# badge.net
KiCad netlist of a schematic drawn in EAGLE
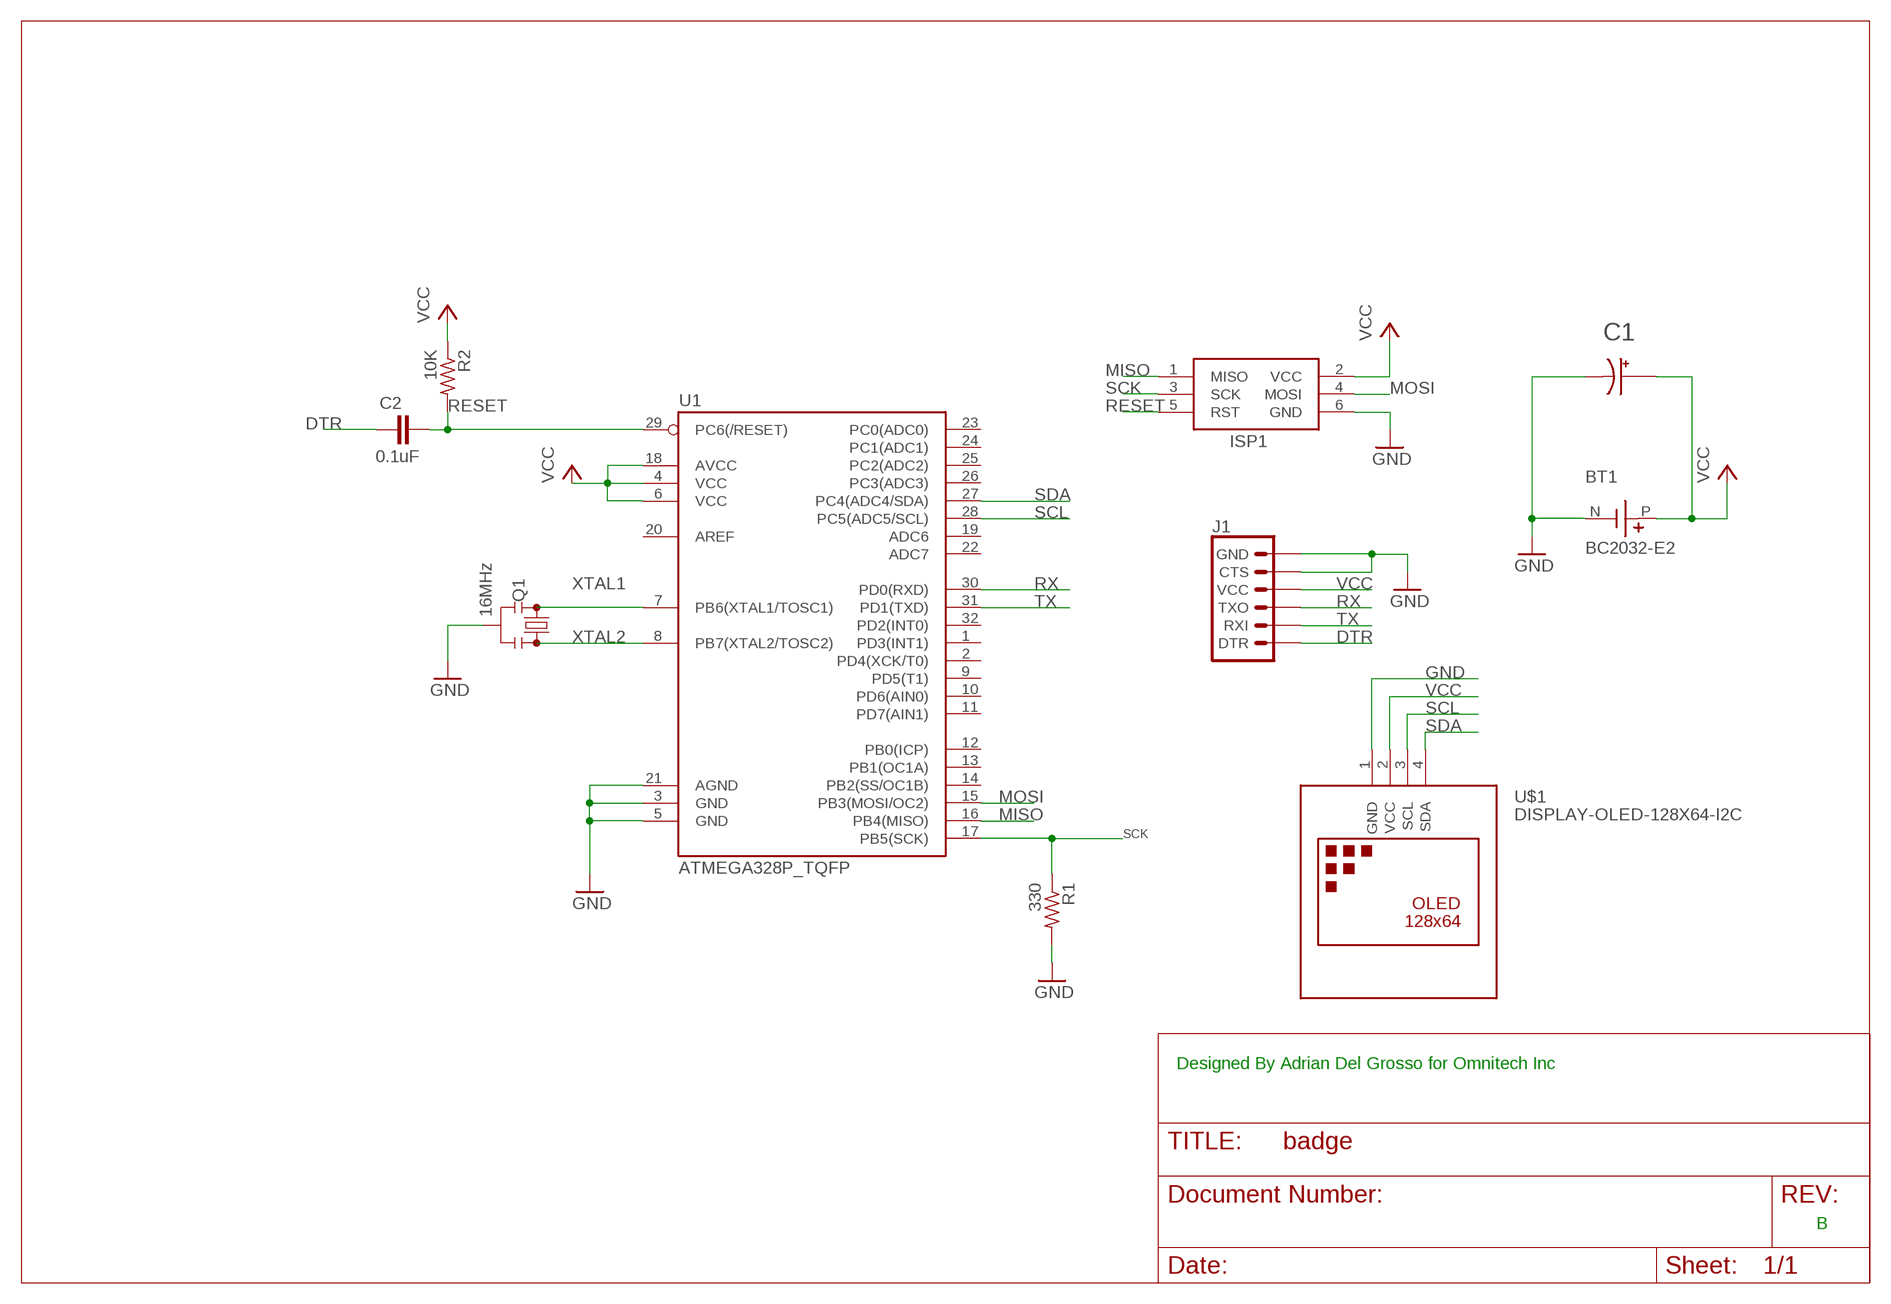
[diagram p0: schematic, sheet 1]

(export (version "E")
  (design (tool "Eeschema 10.0.6"))
  (components
    (comp (ref "BT1")
      (value "BC2032-E2")
      (footprint "eagle-import:MPD_BC2032-E2")
      (fields (field (name "DIGI-KEY_PART_NUMBER") "BC2032-E2-ND") (field (name "MF") "MPD _Memory"))
      (libsource (lib "eagle-import") (part "BC2032-E2"))
    )
    (comp (ref "C1")
      (value "RNE1C101MDS1PX")
      (footprint "eagle-import:CAPPRD200W50D500H1000")
      (fields (field (name "DIGI-KEY_PART_NUMBER") "493-3813-1-ND") (field (name "MF") "Nichicon"))
      (libsource (lib "eagle-import") (part "RNE1C101MDS1PX"))
    )
    (comp (ref "C2")
      (value "0.1uF")
      (footprint "eagle-import:0402")
      (libsource (lib "eagle-import") (part "0.1UF-0402-16V-10%"))
    )
    (comp (ref "ISP1")
      (value "AVRISP-6")
      (footprint "eagle-import:AVRISP")
      (libsource (lib "eagle-import") (part "AVRISP-6"))
    )
    (comp (ref "J1")
      (value "6_PIN_SERIAL_TARGETLONGPADS")
      (footprint "eagle-import:1X06_LONGPADS")
      (libsource (lib "eagle-import") (part "6_PIN_SERIAL_TARGETLONGPADS"))
    )
    (comp (ref "Q1")
      (value "16MHz")
      (footprint "eagle-import:RESONATOR-SMD-3.2X1.3")
      (libsource (lib "eagle-import") (part "RESONATOR-8MHZSMD_3.2X1.3"))
    )
    (comp (ref "R1")
      (value "330")
      (footprint "eagle-import:R0603")
      (libsource (lib "eagle-import") (part "R-US_R0603"))
    )
    (comp (ref "R2")
      (value "10K")
      (footprint "eagle-import:R0603")
      (libsource (lib "eagle-import") (part "R-US_R0603"))
    )
    (comp (ref "U$1")
      (value "DISPLAY-OLED-128X64-I2C")
      (footprint "eagle-import:DISPLAY-OLED-128X64-I2C")
      (libsource (lib "eagle-import") (part "DISPLAY-OLED-128X64-I2C"))
    )
    (comp (ref "U1")
      (value "ATMEGA328P_TQFP")
      (footprint "eagle-import:TQFP32-08")
      (libsource (lib "eagle-import") (part "ATMEGA328P_TQFP"))
    )
  )
  (nets
    (net (code "1") (name "/DTR") (class "Default")
      (node (ref "C2") (pin "1") (pinfunction "1_1") (pintype "passive"))
      (node (ref "J1") (pin "1") (pinfunction "DTR_1") (pintype "passive"))
    )
    (net (code "2") (name "/MISO") (class "Default")
      (node (ref "ISP1") (pin "1") (pinfunction "MISO_1") (pintype "input"))
      (node (ref "U1") (pin "16") (pinfunction "PB4(MISO)_16") (pintype "bidirectional"))
    )
    (net (code "3") (name "/MOSI") (class "Default")
      (node (ref "ISP1") (pin "4") (pinfunction "MOSI_4") (pintype "output"))
      (node (ref "U1") (pin "15") (pinfunction "PB3(MOSI/OC2)_15") (pintype "bidirectional"))
    )
    (net (code "4") (name "/RESET") (class "Default")
      (node (ref "C2") (pin "2") (pinfunction "2_2") (pintype "passive"))
      (node (ref "ISP1") (pin "5") (pinfunction "RST_5") (pintype "output"))
      (node (ref "R2") (pin "2") (pinfunction "2_2") (pintype "passive"))
      (node (ref "U1") (pin "29") (pinfunction "PC6(/RESET)_29") (pintype "bidirectional"))
    )
    (net (code "5") (name "/RX") (class "Default")
      (node (ref "J1") (pin "3") (pinfunction "TXO_3") (pintype "passive"))
      (node (ref "U1") (pin "30") (pinfunction "PD0(RXD)_30") (pintype "bidirectional"))
    )
    (net (code "6") (name "/SCK") (class "Default")
      (node (ref "ISP1") (pin "3") (pinfunction "SCK_3") (pintype "output"))
      (node (ref "R1") (pin "1") (pinfunction "1_1") (pintype "passive"))
      (node (ref "U1") (pin "17") (pinfunction "PB5(SCK)_17") (pintype "bidirectional"))
    )
    (net (code "7") (name "/SCL") (class "Default")
      (node (ref "U$1") (pin "3") (pinfunction "SCL_3") (pintype "bidirectional"))
      (node (ref "U1") (pin "28") (pinfunction "PC5(ADC5/SCL)_28") (pintype "bidirectional"))
    )
    (net (code "8") (name "/SDA") (class "Default")
      (node (ref "U$1") (pin "4") (pinfunction "SDA_4") (pintype "bidirectional"))
      (node (ref "U1") (pin "27") (pinfunction "PC4(ADC4/SDA)_27") (pintype "bidirectional"))
    )
    (net (code "9") (name "/TX") (class "Default")
      (node (ref "J1") (pin "2") (pinfunction "RXI_2") (pintype "passive"))
      (node (ref "U1") (pin "31") (pinfunction "PD1(TXD)_31") (pintype "bidirectional"))
    )
    (net (code "10") (name "/XTAL1") (class "Default")
      (node (ref "Q1") (pin "1") (pinfunction "1_1") (pintype "passive"))
      (node (ref "U1") (pin "7") (pinfunction "PB6(XTAL1/TOSC1)_7") (pintype "bidirectional"))
    )
    (net (code "11") (name "/XTAL2") (class "Default")
      (node (ref "Q1") (pin "3") (pinfunction "3_3") (pintype "passive"))
      (node (ref "U1") (pin "8") (pinfunction "PB7(XTAL2/TOSC2)_8") (pintype "bidirectional"))
    )
    (net (code "12") (name "GND") (class "Default")
      (node (ref "BT1") (pin "N") (pinfunction "N_N") (pintype "passive"))
      (node (ref "C1") (pin "2") (pinfunction "N_2") (pintype "passive"))
      (node (ref "ISP1") (pin "6") (pinfunction "GND_6") (pintype "power_in"))
      (node (ref "J1") (pin "5") (pinfunction "CTS_5") (pintype "passive"))
      (node (ref "J1") (pin "6") (pinfunction "GND_6") (pintype "passive"))
      (node (ref "Q1") (pin "2") (pinfunction "2_2") (pintype "passive"))
      (node (ref "R1") (pin "2") (pinfunction "2_2") (pintype "passive"))
      (node (ref "U$1") (pin "1") (pinfunction "GND_1") (pintype "power_in"))
      (node (ref "U1") (pin "21") (pinfunction "AGND_21") (pintype "bidirectional"))
      (node (ref "U1") (pin "3") (pinfunction "GND_3") (pintype "bidirectional"))
      (node (ref "U1") (pin "5") (pinfunction "GND_5") (pintype "bidirectional"))
    )
    (net (code "13") (name "VCC") (class "Default")
      (node (ref "BT1") (pin "P") (pinfunction "P_P") (pintype "passive"))
      (node (ref "C1") (pin "1") (pinfunction "P_1") (pintype "passive"))
      (node (ref "ISP1") (pin "2") (pinfunction "VCC_2") (pintype "power_in"))
      (node (ref "J1") (pin "4") (pinfunction "VCC_4") (pintype "passive"))
      (node (ref "R2") (pin "1") (pinfunction "1_1") (pintype "passive"))
      (node (ref "U$1") (pin "2") (pinfunction "VCC_2") (pintype "power_in"))
      (node (ref "U1") (pin "18") (pinfunction "AVCC_18") (pintype "bidirectional"))
      (node (ref "U1") (pin "4") (pinfunction "VCC_4") (pintype "bidirectional"))
      (node (ref "U1") (pin "6") (pinfunction "VCC_6") (pintype "bidirectional"))
    )
    (net (code "14") (name "unconnected-(U1-ADC6-Pad19)") (class "Default")
      (node (ref "U1") (pin "19") (pinfunction "ADC6_19") (pintype "bidirectional"))
    )
    (net (code "15") (name "unconnected-(U1-ADC7-Pad22)") (class "Default")
      (node (ref "U1") (pin "22") (pinfunction "ADC7_22") (pintype "bidirectional"))
    )
    (net (code "16") (name "unconnected-(U1-AREF-Pad20)") (class "Default")
      (node (ref "U1") (pin "20") (pinfunction "AREF_20") (pintype "bidirectional"))
    )
    (net (code "17") (name "unconnected-(U1-PB0(ICP)-Pad12)") (class "Default")
      (node (ref "U1") (pin "12") (pinfunction "PB0(ICP)_12") (pintype "bidirectional"))
    )
    (net (code "18") (name "unconnected-(U1-PB1(OC1A)-Pad13)") (class "Default")
      (node (ref "U1") (pin "13") (pinfunction "PB1(OC1A)_13") (pintype "bidirectional"))
    )
    (net (code "19") (name "unconnected-(U1-PB2(SS{slash}OC1B)-Pad14)") (class "Default")
      (node (ref "U1") (pin "14") (pinfunction "PB2(SS/OC1B)_14") (pintype "bidirectional"))
    )
    (net (code "20") (name "unconnected-(U1-PC0(ADC0)-Pad23)") (class "Default")
      (node (ref "U1") (pin "23") (pinfunction "PC0(ADC0)_23") (pintype "bidirectional"))
    )
    (net (code "21") (name "unconnected-(U1-PC1(ADC1)-Pad24)") (class "Default")
      (node (ref "U1") (pin "24") (pinfunction "PC1(ADC1)_24") (pintype "bidirectional"))
    )
    (net (code "22") (name "unconnected-(U1-PC2(ADC2)-Pad25)") (class "Default")
      (node (ref "U1") (pin "25") (pinfunction "PC2(ADC2)_25") (pintype "bidirectional"))
    )
    (net (code "23") (name "unconnected-(U1-PC3(ADC3)-Pad26)") (class "Default")
      (node (ref "U1") (pin "26") (pinfunction "PC3(ADC3)_26") (pintype "bidirectional"))
    )
    (net (code "24") (name "unconnected-(U1-PD2(INT0)-Pad32)") (class "Default")
      (node (ref "U1") (pin "32") (pinfunction "PD2(INT0)_32") (pintype "bidirectional"))
    )
    (net (code "25") (name "unconnected-(U1-PD3(INT1)-Pad1)") (class "Default")
      (node (ref "U1") (pin "1") (pinfunction "PD3(INT1)_1") (pintype "bidirectional"))
    )
    (net (code "26") (name "unconnected-(U1-PD4(XCK{slash}T0)-Pad2)") (class "Default")
      (node (ref "U1") (pin "2") (pinfunction "PD4(XCK/T0)_2") (pintype "bidirectional"))
    )
    (net (code "27") (name "unconnected-(U1-PD5(T1)-Pad9)") (class "Default")
      (node (ref "U1") (pin "9") (pinfunction "PD5(T1)_9") (pintype "bidirectional"))
    )
    (net (code "28") (name "unconnected-(U1-PD6(AIN0)-Pad10)") (class "Default")
      (node (ref "U1") (pin "10") (pinfunction "PD6(AIN0)_10") (pintype "bidirectional"))
    )
    (net (code "29") (name "unconnected-(U1-PD7(AIN1)-Pad11)") (class "Default")
      (node (ref "U1") (pin "11") (pinfunction "PD7(AIN1)_11") (pintype "bidirectional"))
    )
  )
)
